# Sensors.net
KiCad netlist of a schematic drawn in Altium Designer
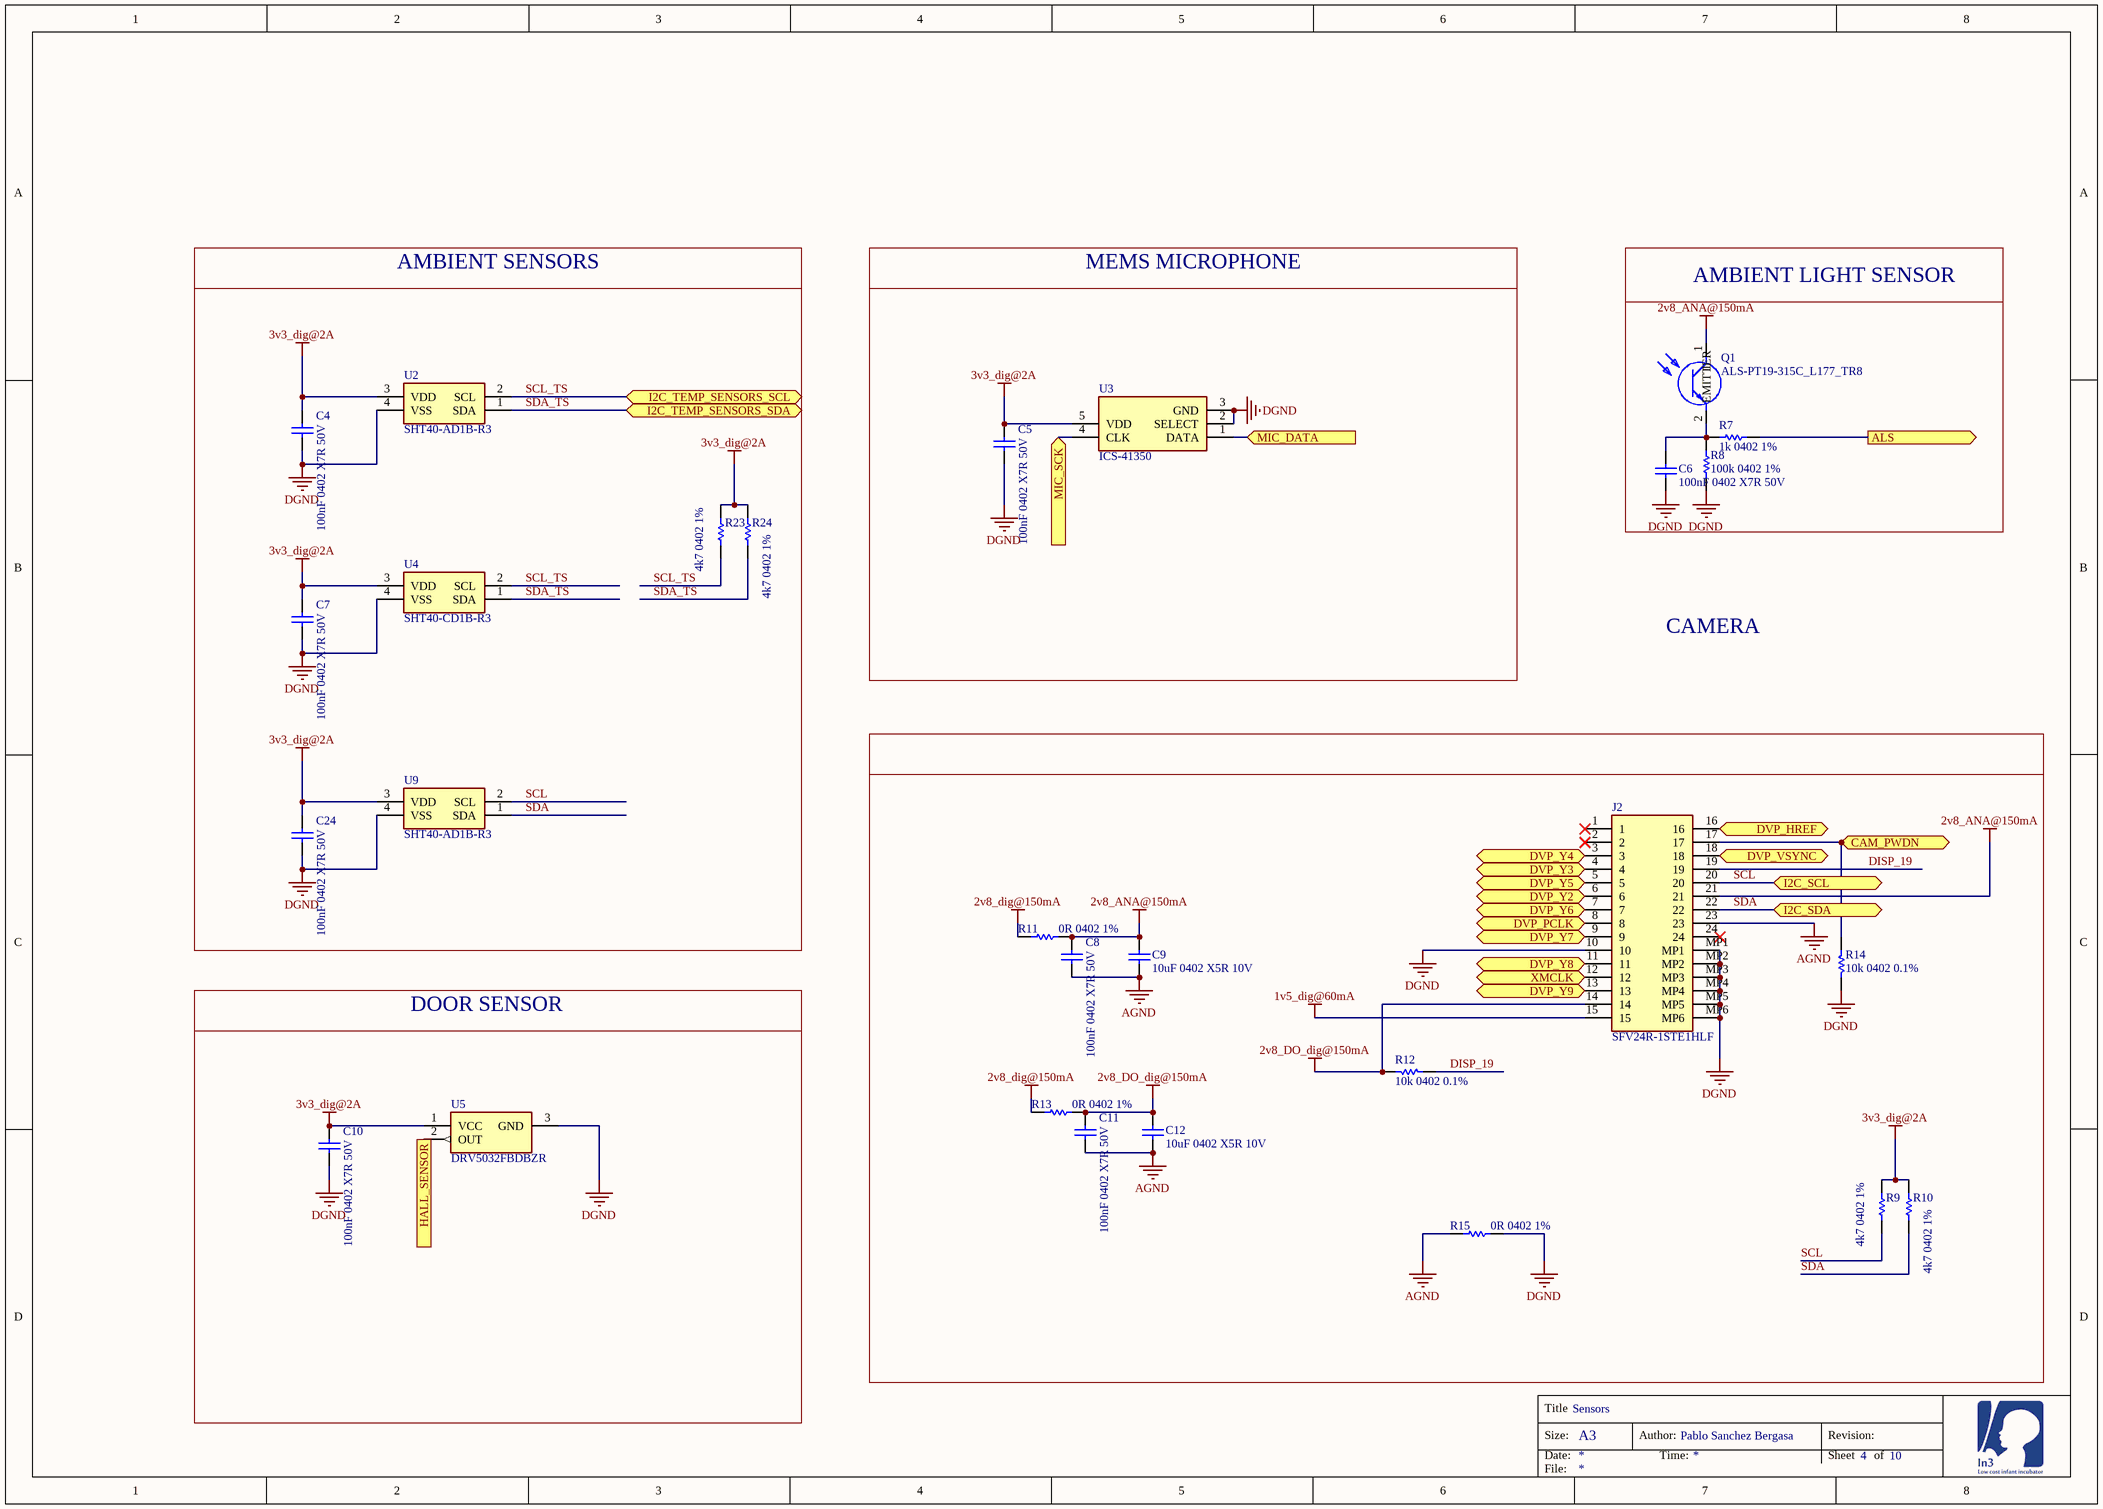
[diagram p0: Sensors.SchDoc]

(export (version "E")
  (design (tool "Eeschema 10.0.6"))
  (components
    (comp (ref "C4")
      (value "100nF 0402 X7R 50V")
      (footprint "CAPC1005X55X25NL5T10")
      (libsource (lib "Altium Content Vault") (part "CAP-NP-2"))
    )
    (comp (ref "C5")
      (value "100nF 0402 X7R 50V")
      (footprint "CAPC1005X55X25NL5T10")
      (libsource (lib "Altium Content Vault") (part "CAP-NP-2"))
    )
    (comp (ref "C6")
      (value "100nF 0402 X7R 50V")
      (footprint "CAPC1005X55X25NL5T10")
      (libsource (lib "Altium Content Vault") (part "CAP-NP-2"))
    )
    (comp (ref "C7")
      (value "100nF 0402 X7R 50V")
      (footprint "CAPC1005X55X25NL5T10")
      (libsource (lib "Altium Content Vault") (part "CAP-NP-2"))
    )
    (comp (ref "C8")
      (value "100nF 0402 X7R 50V")
      (footprint "CAPC1005X55X25NL5T10")
      (libsource (lib "Altium Content Vault") (part "CAP-NP-2"))
    )
    (comp (ref "C9")
      (value "10uF 0402 X5R 10V")
      (footprint "CAPC1005X55X25NL5T10")
      (libsource (lib "Altium Content Vault") (part "CAP-NP-2"))
    )
    (comp (ref "C10")
      (value "100nF 0402 X7R 50V")
      (footprint "CAPC1005X55X25NL5T10")
      (libsource (lib "Altium Content Vault") (part "CAP-NP-2"))
    )
    (comp (ref "C11")
      (value "100nF 0402 X7R 50V")
      (footprint "CAPC1005X55X25NL5T10")
      (libsource (lib "Altium Content Vault") (part "CAP-NP-2"))
    )
    (comp (ref "C12")
      (value "10uF 0402 X5R 10V")
      (footprint "CAPC1005X55X25NL5T10")
      (libsource (lib "Altium Content Vault") (part "CAP-NP-2"))
    )
    (comp (ref "C24")
      (value "100nF 0402 X7R 50V")
      (footprint "CAPC1005X55X25NL5T10")
      (libsource (lib "Altium Content Vault") (part "CAP-NP-2"))
    )
    (comp (ref "J2")
      (value "SFV24R-1STE1HLF")
      (footprint "SamacSys:SFV24R1STE1HLF")
      (description "Connector")
      (libsource (lib "*") (part "SFV24R-1STE1HLF"))
    )
    (comp (ref "Q1")
      (value "ALS-PT19-315C_L177_TR8")
      (footprint "SamacSys:ALSPT19315CL177TR8")
      (description "Phototransistor")
      (fields
        (field (name "MANUFACTURER_PART_NUMBER") "ALS-PT19-315C/L177/TR8")
        (field (name "MOUSER PART NUMBER") "638-ALSPT19315CL177")
      )
      (libsource (lib "SamacSys") (part "ALS-PT19-315C_L177_TR8"))
    )
    (comp (ref "R7")
      (value "1k 0402 1%")
      (footprint "RESC1005X40X25ML05T10")
      (libsource (lib "Altium Content Vault") (part "RES"))
    )
    (comp (ref "R8")
      (value "100k 0402 1%")
      (footprint "RESC1005X40X25ML05T10")
      (libsource (lib "Altium Content Vault") (part "RES"))
    )
    (comp (ref "R9")
      (value "4k7 0402 1%")
      (footprint "RESC1005X40X25ML05T10")
      (libsource (lib "Altium Content Vault") (part "RES"))
    )
    (comp (ref "R10")
      (value "4k7 0402 1%")
      (footprint "RESC1005X40X25ML05T10")
      (libsource (lib "Altium Content Vault") (part "RES"))
    )
    (comp (ref "R11")
      (value "0R 0402 1%")
      (footprint "RESC1005X40X25ML05T10")
      (libsource (lib "Altium Content Vault") (part "RES"))
    )
    (comp (ref "R12")
      (value "10k 0402 0.1%")
      (footprint "RESC1005X40X25ML05T10")
      (libsource (lib "Altium Content Vault") (part "RES"))
    )
    (comp (ref "R13")
      (value "0R 0402 1%")
      (footprint "RESC1005X40X25ML05T10")
      (libsource (lib "Altium Content Vault") (part "RES"))
    )
    (comp (ref "R14")
      (value "10k 0402 0.1%")
      (footprint "RESC1005X40X25ML05T10")
      (libsource (lib "Altium Content Vault") (part "RES"))
    )
    (comp (ref "R15")
      (value "0R 0402 1%")
      (footprint "RESC1005X40X25ML05T10")
      (libsource (lib "Altium Content Vault") (part "RES"))
    )
    (comp (ref "R23")
      (value "4k7 0402 1%")
      (footprint "RESC1005X40X25ML05T10")
      (libsource (lib "Altium Content Vault") (part "RES"))
    )
    (comp (ref "R24")
      (value "4k7 0402 1%")
      (footprint "RESC1005X40X25ML05T10")
      (libsource (lib "Altium Content Vault") (part "RES"))
    )
    (comp (ref "U2")
      (value "SHT40-AD1B-R3")
      (footprint "SamacSys:SHT40AD1BR3")
      (description "Integrated Circuit")
      (fields (field (name "MOUSER PART NUMBER") "403-SHT40-AD1B-R3"))
      (libsource (lib "*") (part "SHT40-AD1B-R3"))
    )
    (comp (ref "U3")
      (value "ICS-41350")
      (footprint "SamacSys:ICS41352")
      (description "Integrated Circuit")
      (fields (field (name "MOUSER PART NUMBER") "410-ICS-41350"))
      (libsource (lib "*") (part "ICS-41350"))
    )
    (comp (ref "U4")
      (value "SHT40-CD1B-R3")
      (footprint "SamacSys:SHT40CD1BR3")
      (description "Integrated Circuit")
      (fields (field (name "MOUSER PART NUMBER") "403-SHT40-CD1B-R3"))
      (libsource (lib "*") (part "SHT40-CD1B-R3"))
    )
    (comp (ref "U5")
      (value "DRV5032FBDBZR")
      (footprint "SamacSys:SOT95P237X95-3N")
      (description "Integrated Circuit")
      (fields (field (name "MOUSER PART NUMBER") "595-DRV5032FBDBZR"))
      (libsource (lib "*") (part "DRV5032FBDBZR"))
    )
    (comp (ref "U9")
      (value "SHT40-AD1B-R3")
      (footprint "SamacSys:SHT40AD1BR3")
      (description "Integrated Circuit")
      (fields (field (name "MOUSER PART NUMBER") "403-SHT40-AD1B-R3"))
      (libsource (lib "*") (part "SHT40-AD1B-R3"))
    )
  )
  (nets
    (net (code "1") (name "/ALS") (class "Default")
      (node (ref "R7") (pin "2") (pinfunction "2_2") (pintype "passive"))
    )
    (net (code "2") (name "/CAM_PWDN") (class "Default")
      (node (ref "J2") (pin "17") (pinfunction "17_17") (pintype "passive"))
      (node (ref "R14") (pin "1") (pinfunction "1_1") (pintype "passive"))
    )
    (net (code "3") (name "/DISP_19") (class "Default")
      (node (ref "J2") (pin "19") (pinfunction "19_19") (pintype "passive"))
      (node (ref "R12") (pin "1") (pinfunction "1_1") (pintype "passive"))
    )
    (net (code "4") (name "/DVP_HREF") (class "Default")
      (node (ref "J2") (pin "16") (pinfunction "16_16") (pintype "passive"))
    )
    (net (code "5") (name "/DVP_PCLK") (class "Default")
      (node (ref "J2") (pin "8") (pinfunction "8_8") (pintype "passive"))
    )
    (net (code "6") (name "/DVP_VSYNC") (class "Default")
      (node (ref "J2") (pin "18") (pinfunction "18_18") (pintype "passive"))
    )
    (net (code "7") (name "/DVP_Y2") (class "Default")
      (node (ref "J2") (pin "6") (pinfunction "6_6") (pintype "passive"))
    )
    (net (code "8") (name "/DVP_Y3") (class "Default")
      (node (ref "J2") (pin "4") (pinfunction "4_4") (pintype "passive"))
    )
    (net (code "9") (name "/DVP_Y4") (class "Default")
      (node (ref "J2") (pin "3") (pinfunction "3_3") (pintype "passive"))
    )
    (net (code "10") (name "/DVP_Y5") (class "Default")
      (node (ref "J2") (pin "5") (pinfunction "5_5") (pintype "passive"))
    )
    (net (code "11") (name "/DVP_Y6") (class "Default")
      (node (ref "J2") (pin "7") (pinfunction "7_7") (pintype "passive"))
    )
    (net (code "12") (name "/DVP_Y7") (class "Default")
      (node (ref "J2") (pin "9") (pinfunction "9_9") (pintype "passive"))
    )
    (net (code "13") (name "/DVP_Y8") (class "Default")
      (node (ref "J2") (pin "11") (pinfunction "11_11") (pintype "passive"))
    )
    (net (code "14") (name "/DVP_Y9") (class "Default")
      (node (ref "J2") (pin "13") (pinfunction "13_13") (pintype "passive"))
    )
    (net (code "15") (name "/HALL_SENSOR") (class "Default")
      (node (ref "U5") (pin "2") (pinfunction "OUT_2") (pintype "output"))
    )
    (net (code "16") (name "/MIC_DATA") (class "Default")
      (node (ref "U3") (pin "1") (pinfunction "DATA_1") (pintype "passive"))
    )
    (net (code "17") (name "/MIC_SCK") (class "Default")
      (node (ref "U3") (pin "4") (pinfunction "CLK_4") (pintype "passive"))
    )
    (net (code "18") (name "/SCL") (class "Default")
      (node (ref "J2") (pin "20") (pinfunction "20_20") (pintype "passive"))
      (node (ref "R9") (pin "2") (pinfunction "2_2") (pintype "passive"))
      (node (ref "U9") (pin "2") (pinfunction "SCL_2") (pintype "passive"))
    )
    (net (code "19") (name "/SCL_TS") (class "Default")
      (node (ref "R23") (pin "2") (pinfunction "2_2") (pintype "passive"))
      (node (ref "U2") (pin "2") (pinfunction "SCL_2") (pintype "passive"))
      (node (ref "U4") (pin "2") (pinfunction "SCL_2") (pintype "passive"))
    )
    (net (code "20") (name "/SDA") (class "Default")
      (node (ref "J2") (pin "22") (pinfunction "22_22") (pintype "passive"))
      (node (ref "R10") (pin "2") (pinfunction "2_2") (pintype "passive"))
      (node (ref "U9") (pin "1") (pinfunction "SDA_1") (pintype "passive"))
    )
    (net (code "21") (name "/SDA_TS") (class "Default")
      (node (ref "R24") (pin "2") (pinfunction "2_2") (pintype "passive"))
      (node (ref "U2") (pin "1") (pinfunction "SDA_1") (pintype "passive"))
      (node (ref "U4") (pin "1") (pinfunction "SDA_1") (pintype "passive"))
    )
    (net (code "22") (name "/XMCLK") (class "Default")
      (node (ref "J2") (pin "12") (pinfunction "12_12") (pintype "passive"))
    )
    (net (code "23") (name "1v5_dig@60mA") (class "Default")
      (node (ref "J2") (pin "15") (pinfunction "15_15") (pintype "passive"))
    )
    (net (code "24") (name "2v8_ANA@150mA") (class "Default")
      (node (ref "C8") (pin "2") (pinfunction "2_2") (pintype "passive"))
      (node (ref "C9") (pin "1") (pinfunction "1_1") (pintype "passive"))
      (node (ref "J2") (pin "21") (pinfunction "21_21") (pintype "passive"))
      (node (ref "Q1") (pin "1") (pinfunction "1_1") (pintype "passive"))
      (node (ref "R11") (pin "1") (pinfunction "1_1") (pintype "passive"))
    )
    (net (code "25") (name "2v8_DO_dig@150mA") (class "Default")
      (node (ref "C11") (pin "2") (pinfunction "2_2") (pintype "passive"))
      (node (ref "C12") (pin "1") (pinfunction "1_1") (pintype "passive"))
      (node (ref "J2") (pin "14") (pinfunction "14_14") (pintype "passive"))
      (node (ref "R12") (pin "2") (pinfunction "2_2") (pintype "passive"))
      (node (ref "R13") (pin "1") (pinfunction "1_1") (pintype "passive"))
    )
    (net (code "26") (name "2v8_dig@150mA") (class "Default")
      (node (ref "R11") (pin "2") (pinfunction "2_2") (pintype "passive"))
      (node (ref "R13") (pin "2") (pinfunction "2_2") (pintype "passive"))
    )
    (net (code "27") (name "3v3_dig@2A") (class "Default")
      (node (ref "C10") (pin "2") (pinfunction "2_2") (pintype "passive"))
      (node (ref "C24") (pin "2") (pinfunction "2_2") (pintype "passive"))
      (node (ref "C4") (pin "2") (pinfunction "2_2") (pintype "passive"))
      (node (ref "C5") (pin "2") (pinfunction "2_2") (pintype "passive"))
      (node (ref "C7") (pin "2") (pinfunction "2_2") (pintype "passive"))
      (node (ref "R10") (pin "1") (pinfunction "1_1") (pintype "passive"))
      (node (ref "R23") (pin "1") (pinfunction "1_1") (pintype "passive"))
      (node (ref "R24") (pin "1") (pinfunction "1_1") (pintype "passive"))
      (node (ref "R9") (pin "1") (pinfunction "1_1") (pintype "passive"))
      (node (ref "U2") (pin "3") (pinfunction "VDD_3") (pintype "passive"))
      (node (ref "U3") (pin "5") (pinfunction "VDD_5") (pintype "passive"))
      (node (ref "U4") (pin "3") (pinfunction "VDD_3") (pintype "passive"))
      (node (ref "U5") (pin "1") (pinfunction "VCC_1") (pintype "power_in"))
      (node (ref "U9") (pin "3") (pinfunction "VDD_3") (pintype "passive"))
    )
    (net (code "28") (name "AGND") (class "Default")
      (node (ref "C11") (pin "1") (pinfunction "1_1") (pintype "passive"))
      (node (ref "C12") (pin "2") (pinfunction "2_2") (pintype "passive"))
      (node (ref "C8") (pin "1") (pinfunction "1_1") (pintype "passive"))
      (node (ref "C9") (pin "2") (pinfunction "2_2") (pintype "passive"))
      (node (ref "J2") (pin "23") (pinfunction "23_23") (pintype "passive"))
      (node (ref "R15") (pin "2") (pinfunction "2_2") (pintype "passive"))
    )
    (net (code "29") (name "DGND") (class "Default")
      (node (ref "C10") (pin "1") (pinfunction "1_1") (pintype "passive"))
      (node (ref "C24") (pin "1") (pinfunction "1_1") (pintype "passive"))
      (node (ref "C4") (pin "1") (pinfunction "1_1") (pintype "passive"))
      (node (ref "C5") (pin "1") (pinfunction "1_1") (pintype "passive"))
      (node (ref "C6") (pin "2") (pinfunction "2_2") (pintype "passive"))
      (node (ref "C7") (pin "1") (pinfunction "1_1") (pintype "passive"))
      (node (ref "J2") (pin "10") (pinfunction "10_10") (pintype "passive"))
      (node (ref "J2") (pin "MP1") (pinfunction "MP1_MP1") (pintype "passive"))
      (node (ref "J2") (pin "MP2") (pinfunction "MP2_MP2") (pintype "passive"))
      (node (ref "J2") (pin "MP3") (pinfunction "MP3_MP3") (pintype "passive"))
      (node (ref "J2") (pin "MP4") (pinfunction "MP4_MP4") (pintype "passive"))
      (node (ref "J2") (pin "MP5") (pinfunction "MP5_MP5") (pintype "passive"))
      (node (ref "J2") (pin "MP6") (pinfunction "MP6_MP6") (pintype "passive"))
      (node (ref "R14") (pin "2") (pinfunction "2_2") (pintype "passive"))
      (node (ref "R15") (pin "1") (pinfunction "1_1") (pintype "passive"))
      (node (ref "R8") (pin "2") (pinfunction "2_2") (pintype "passive"))
      (node (ref "U2") (pin "4") (pinfunction "VSS_4") (pintype "passive"))
      (node (ref "U3") (pin "2") (pinfunction "SELECT_2") (pintype "passive"))
      (node (ref "U3") (pin "3") (pinfunction "GND_3") (pintype "passive"))
      (node (ref "U4") (pin "4") (pinfunction "VSS_4") (pintype "passive"))
      (node (ref "U5") (pin "3") (pinfunction "GND_3") (pintype "power_in"))
      (node (ref "U9") (pin "4") (pinfunction "VSS_4") (pintype "passive"))
    )
    (net (code "30") (name "Net-(Q1-EMITTER)") (class "Default")
      (node (ref "C6") (pin "1") (pinfunction "1_1") (pintype "passive"))
      (node (ref "Q1") (pin "2") (pinfunction "EMITTER_2") (pintype "passive"))
      (node (ref "R7") (pin "1") (pinfunction "1_1") (pintype "passive"))
      (node (ref "R8") (pin "1") (pinfunction "1_1") (pintype "passive"))
    )
    (net (code "31") (name "unconnected-(J2-Pad1)") (class "Default")
      (node (ref "J2") (pin "1") (pinfunction "1_1") (pintype "passive+no_connect"))
    )
    (net (code "32") (name "unconnected-(J2-Pad2)") (class "Default")
      (node (ref "J2") (pin "2") (pinfunction "2_2") (pintype "passive+no_connect"))
    )
    (net (code "33") (name "unconnected-(J2-Pad24)") (class "Default")
      (node (ref "J2") (pin "24") (pinfunction "24_24") (pintype "passive+no_connect"))
    )
  )
)
